# LM1117_3V3_800mA.net
KiCad netlist of a schematic drawn in Altium Designer
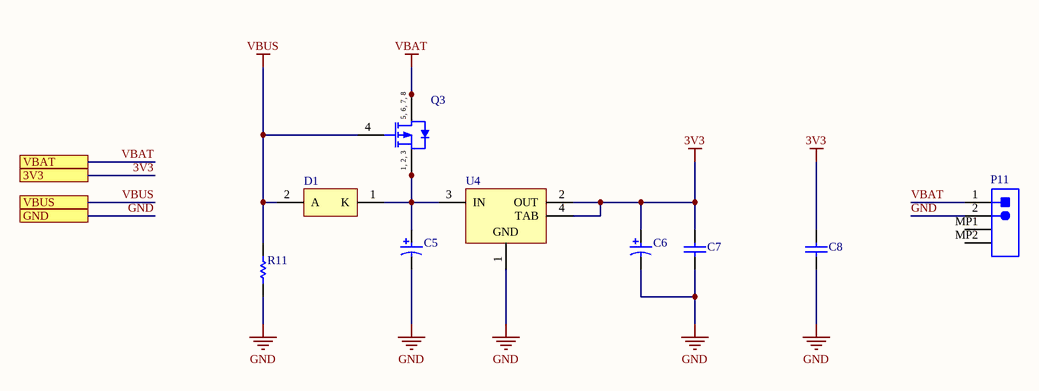
[diagram p0: LM1117_3V3_800mA.SchDoc]

(export (version "E")
  (design (tool "Eeschema 10.0.6"))
  (components
    (comp (ref "C5")
      (value "T491A106K016AT")
      (footprint "KEMT-A-3216-18-2_N")
      (description "Capacitor, Tantalum, 10 uF, +/- 10%, 16 V, -55 to 125 degC, 2-Pin SMD (1206), RoHS, Tape and Reel")
      (fields (field (name "VOLTAGE") "16VDC") (field (name "MANUFACTURER") "Kemet"))
      (libsource (lib "Altium Content Vault") (part "CAP-P-2"))
    )
    (comp (ref "C6")
      (value "T491A106K016AT")
      (footprint "KEMT-A-3216-18-2_N")
      (description "Capacitor, Tantalum, 10 uF, +/- 10%, 16 V, -55 to 125 degC, 2-Pin SMD (1206), RoHS, Tape and Reel")
      (fields (field (name "VOLTAGE") "16VDC") (field (name "MANUFACTURER") "Kemet"))
      (libsource (lib "Altium Content Vault") (part "CAP-P-2"))
    )
    (comp (ref "C7")
      (value "C0805C105K4RAC7800")
      (footprint "CAPC2013X145X50ML20T25")
      (description "1µF ±10% 16V Ceramic Capacitor X7R 0805 (2012 Metric)")
      (fields (field (name "MANUFACTURER") "Kemet"))
      (libsource (lib "Altium Content Vault") (part "CAP"))
    )
    (comp (ref "C8")
      (value "C0805C106K4PACTU")
      (footprint "CAPC2013X140X50ML20T25")
      (description "10µF ±10% 16V Ceramic Capacitor X5R 0805 (2012 Metric)")
      (fields (field (name "PART NUMBER") "CL21A106KOQNNNG"))
      (libsource (lib "Altium Content Vault") (part "CAP"))
    )
    (comp (ref "D1")
      (value "MBR120ESFT1G")
      (footprint "ONSC-SOD-123FL-2-498_V")
      (description "Schottky Power Rectifier, 2-Pin SOD-123, Pb-Free, Tape and Reel")
      (fields (field (name "MANUFACTURER") "On Semiconductor"))
      (libsource (lib "Altium Content Vault") (part "ONSC-D-K1A2-2_A"))
    )
    (comp (ref "P11")
      (value "S2B-PH-SM4-TB(LF)(SN)")
      (footprint "JST- S2B-PH-SM4-TB(LF)(SN)-2_V")
      (description "Male Header, Pitch 2 mm, 1 x 2 Position, Height 5.5 mm, -25 to 85 degC, RoHS, Tape and Reel")
      (libsource (lib "Altium Content Vault") (part "CN-1P-2M-R2"))
    )
    (comp (ref "Q3")
      (value "BSZ086P03NS3 G")
      (footprint "INF-PG-TSDSON-8-1_V")
      (fields (field (name "MANUFACTURER") "Infineon"))
      (libsource (lib "Altium Content Vault") (part "INF-PEMOS-SSSGDDDD-8"))
    )
    (comp (ref "R11")
      (value "ERA6AEB104V")
      (footprint "RESC2013X60X40ML20T25")
      (description "100 kOhms ±0.1% 0.125W, 1/8W Chip Resistor 0805 (2012 Metric) Automotive AEC-Q200 Thin Film")
      (fields (field (name "MANUFACTURER") "Panasonic"))
      (libsource (lib "Altium Content Vault") (part "RES"))
    )
    (comp (ref "U4")
      (value "LM1117MPX-3.3/NOPB")
      (footprint "DCY0004A_N")
      (description "800mA Low-Dropout Linear Regulator, 4-pin SOT-223, Pb-Free")
      (fields (field (name "MANUFACTURER") "Texas Instruments"))
      (libsource (lib "Altium Content Vault") (part "PM-REG-LM1086-SOT4"))
    )
  )
  (nets
    (net (code "1") (name "3V3") (class "Default")
      (node (ref "C6") (pin "1") (pinfunction "1_1") (pintype "passive"))
      (node (ref "C7") (pin "2") (pinfunction "2_2") (pintype "passive"))
      (node (ref "C8") (pin "2") (pinfunction "2_2") (pintype "passive"))
      (node (ref "U4") (pin "2") (pinfunction "OUT_2") (pintype "power_in"))
      (node (ref "U4") (pin "4") (pinfunction "TAB_4") (pintype "power_in"))
    )
    (net (code "2") (name "GND") (class "Default")
      (node (ref "C5") (pin "2") (pinfunction "2_2") (pintype "passive"))
      (node (ref "C6") (pin "2") (pinfunction "2_2") (pintype "passive"))
      (node (ref "C7") (pin "1") (pinfunction "1_1") (pintype "passive"))
      (node (ref "C8") (pin "1") (pinfunction "1_1") (pintype "passive"))
      (node (ref "P11") (pin "2") (pinfunction "2_2") (pintype "passive"))
      (node (ref "R11") (pin "1") (pinfunction "1_1") (pintype "passive"))
      (node (ref "U4") (pin "1") (pinfunction "GND_1") (pintype "power_in"))
    )
    (net (code "3") (name "Net-(D1-K)") (class "Default")
      (node (ref "C5") (pin "1") (pinfunction "1_1") (pintype "passive"))
      (node (ref "D1") (pin "1") (pinfunction "K_1") (pintype "passive"))
      (node (ref "Q3") (pin "1") (pinfunction "SOURCE_1") (pintype "passive"))
      (node (ref "Q3") (pin "2") (pinfunction "SOURCE_2") (pintype "passive"))
      (node (ref "Q3") (pin "3") (pinfunction "SOURCE_3") (pintype "passive"))
      (node (ref "U4") (pin "3") (pinfunction "IN_3") (pintype "power_in"))
    )
    (net (code "4") (name "VBAT") (class "Default")
      (node (ref "P11") (pin "1") (pinfunction "1_1") (pintype "passive"))
      (node (ref "Q3") (pin "5") (pinfunction "DRAIN_5") (pintype "passive"))
      (node (ref "Q3") (pin "6") (pinfunction "DRAIN_6") (pintype "passive"))
      (node (ref "Q3") (pin "7") (pinfunction "DRAIN_7") (pintype "passive"))
      (node (ref "Q3") (pin "8") (pinfunction "DRAIN_8") (pintype "passive"))
    )
    (net (code "5") (name "VBUS") (class "Default")
      (node (ref "D1") (pin "2") (pinfunction "A_2") (pintype "passive"))
      (node (ref "Q3") (pin "4") (pinfunction "GATE_4") (pintype "passive"))
      (node (ref "R11") (pin "2") (pinfunction "2_2") (pintype "passive"))
    )
    (net (code "6") (name "unconnected-(P11-PadMP1)") (class "Default")
      (node (ref "P11") (pin "MP1") (pinfunction "MP1_MP1") (pintype "passive"))
    )
    (net (code "7") (name "unconnected-(P11-PadMP2)") (class "Default")
      (node (ref "P11") (pin "MP2") (pinfunction "MP2_MP2") (pintype "passive"))
    )
  )
)
